# BSPD_v2.net
KiCad netlist of a schematic drawn in Altium Designer
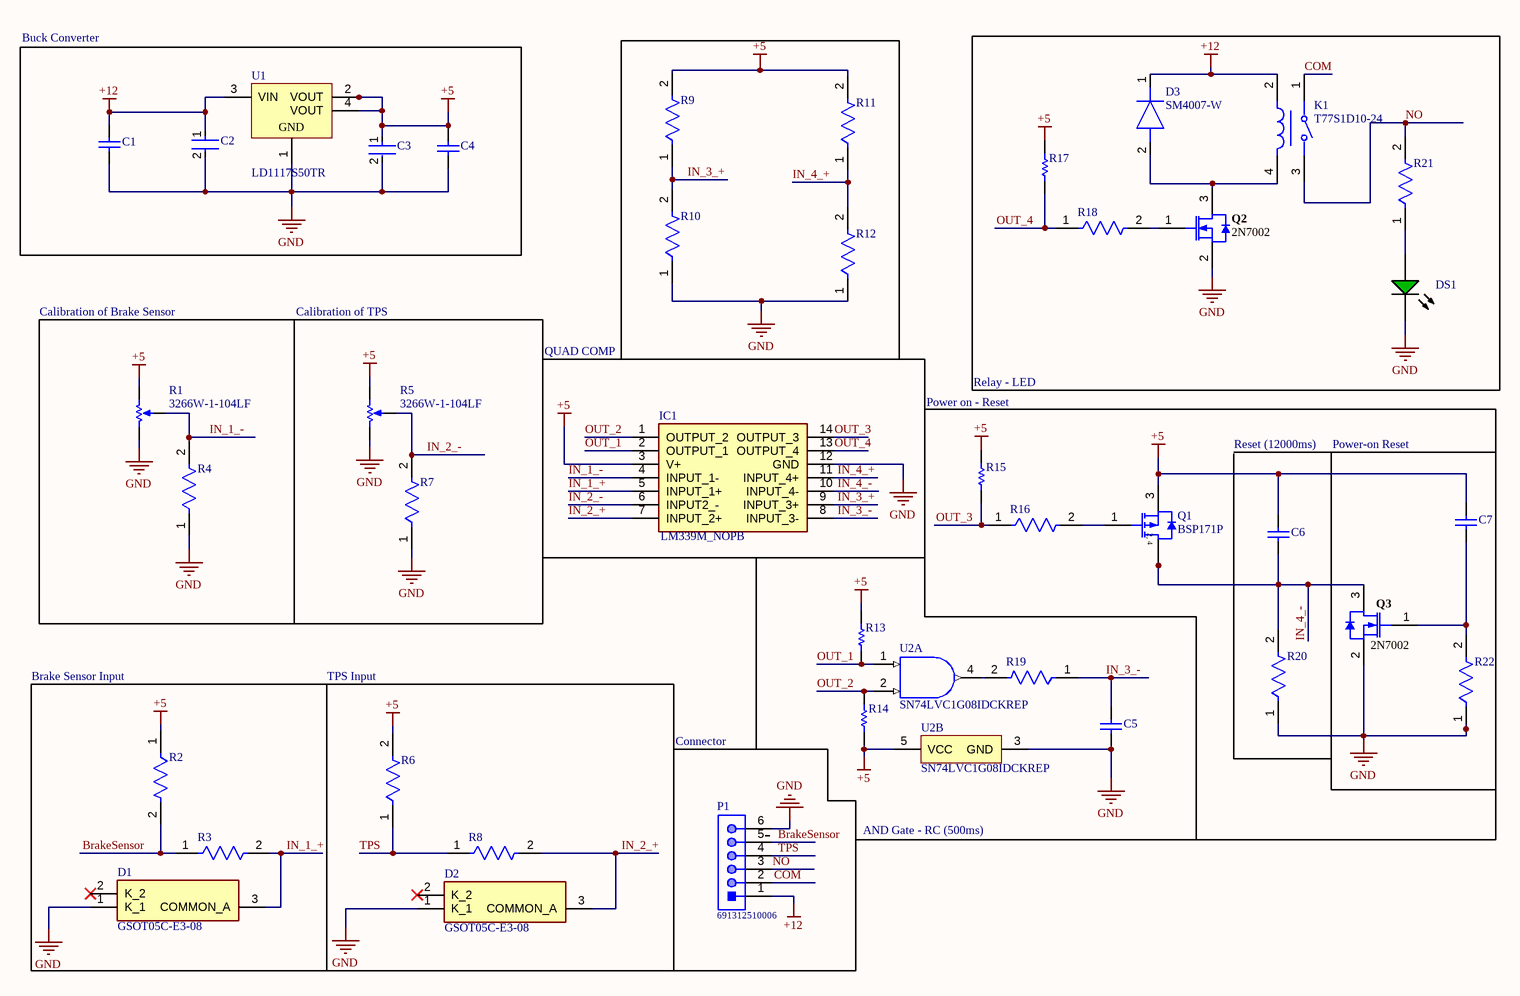
[diagram p0: BSPD v2.SchDoc]

(export (version "E")
  (design (tool "Eeschema 10.0.6"))
  (components
    (comp (ref "C1")
      (value "C1206C106K8RACTU")
      (footprint "CAPC3216X180X50LL20T25")
      (description "Chip Capacitor, 10 uF, +/- 10%, 10 V, -55 to 125 degC, 1206 (3216 Metric), RoHS, Tape and Reel")
      (fields (field (name "TOLERANCE") "10%") (field (name "MANUFACTURER") "Kemet"))
      (libsource (lib "Altium Content Vault") (part "CAP-NP-2"))
    )
    (comp (ref "C2")
      (value "CL21B104KBCNNNC")
      (footprint "FP-CL21-IPC_C")
      (description "CL21 Series 0805 100nF 50V ±10% Tolerance X7R Multilayer Ceramic Chip Capacitor")
      (fields (field (name "TOLERANCE") "10%") (field (name "VOLTAGE") "50V"))
      (libsource (lib "Altium Content Vault") (part "b4654b650e69147ec39a6b967a45e02"))
    )
    (comp (ref "C3")
      (value "CL21B104KBCNNNC")
      (footprint "FP-CL21-IPC_C")
      (description "CL21 Series 0805 100nF 50V ±10% Tolerance X7R Multilayer Ceramic Chip Capacitor")
      (fields (field (name "TOLERANCE") "10%") (field (name "VOLTAGE") "50V"))
      (libsource (lib "Altium Content Vault") (part "b4654b650e69147ec39a6b967a45e02"))
    )
    (comp (ref "C4")
      (value "C1206C106K8RACTU")
      (footprint "CAPC3216X180X50LL20T25")
      (description "Chip Capacitor, 10 uF, +/- 10%, 10 V, -55 to 125 degC, 1206 (3216 Metric), RoHS, Tape and Reel")
      (fields (field (name "TOLERANCE") "10%") (field (name "MANUFACTURER") "Kemet"))
      (libsource (lib "Altium Content Vault") (part "CAP-NP-2"))
    )
    (comp (ref "C5")
      (value "C1206C106K8RACTU")
      (footprint "CAPC3216X180X50LL20T25")
      (description "Chip Capacitor, 10 uF, +/- 10%, 10 V, -55 to 125 degC, 1206 (3216 Metric), RoHS, Tape and Reel")
      (fields (field (name "TOLERANCE") "10%") (field (name "MANUFACTURER") "Kemet"))
      (libsource (lib "Altium Content Vault") (part "CAP-NP-2"))
    )
    (comp (ref "C6")
      (value "C1206C106K8RACTU")
      (footprint "CAPC3216X180X50LL20T25")
      (description "Chip Capacitor, 10 uF, +/- 10%, 10 V, -55 to 125 degC, 1206 (3216 Metric), RoHS, Tape and Reel")
      (fields (field (name "TOLERANCE") "10%") (field (name "MANUFACTURER") "Kemet"))
      (libsource (lib "Altium Content Vault") (part "CAP-NP-2"))
    )
    (comp (ref "C7")
      (value "C1206C106K8RACTU")
      (footprint "CAPC3216X180X50LL20T25")
      (description "Chip Capacitor, 100 nF, +/- 10%, 10 V, -55 to 125 degC, 1206 (3216 Metric), RoHS, Tape and Reel")
      (fields (field (name "TOLERANCE") "10%") (field (name "MANUFACTURER") "Kemet"))
      (libsource (lib "Altium Content Vault") (part "CAP-NP-2"))
    )
    (comp (ref "D1")
      (value "GSOT05C-E3-08")
      (footprint "SamacSys:SOT95P248X115-3N")
      (description "Diode ESD (Uni-directional)")
      (fields (field (name "MOUSER PART NUMBER") "78-GSOT05C-E3-08"))
      (libsource (lib "*") (part "GSOT05C-E3-08"))
    )
    (comp (ref "D2")
      (value "GSOT05C-E3-08")
      (footprint "SamacSys:SOT95P248X115-3N")
      (description "Diode ESD (Uni-directional)")
      (fields (field (name "MOUSER PART NUMBER") "78-GSOT05C-E3-08"))
      (libsource (lib "*") (part "GSOT05C-E3-08"))
    )
    (comp (ref "D3")
      (value "SM4007-W")
      (footprint "SamacSys:SM4007W")
      (description "Diode")
      (fields (field (name "MOUSER PART NUMBER") "583-SM4007"))
      (libsource (lib "*") (part "SM4007-W"))
    )
    (comp (ref "DS1")
      (value "LTST-C170KGKT")
      (footprint "LTST-LTST-C170KGKT-2_V")
      (description "Ultra Bright AlInGaP Chip LED, 75 mW, -55 to 85 degC, 2-Pin SMD (0805), RoHS, Tape and Reel")
      (fields (field (name "MANUFACTURER") "Lite-On"))
      (libsource (lib "Altium Content Vault") (part "LED-GREEN-KA-2"))
    )
    (comp (ref "IC1")
      (value "LM339M_NOPB")
      (footprint "SamacSys:SOIC127P600X175-14N")
      (description "Integrated Circuit")
      (fields
        (field (name "MANUFACTURER_PART_NUMBER") "LM339M/NOPB")
        (field (name "MOUSER PART NUMBER") "926-LM339M/NOPB")
      )
      (libsource (lib "*") (part "LM339M_NOPB"))
    )
    (comp (ref "K1")
      (value "T77S1D10-24")
      (footprint "FP-T77S1D10-24-MFG")
      (description "RELAY GEN PURPOSE SPST 10A 24V")
      (libsource (lib "Altium Content Vault") (part "efdf740da079d6e8343da2175463948"))
    )
    (comp (ref "P1")
      (value "691312510006")
      (footprint "691312510006")
      (description "Serie 312 - 5.08mm Open Horizontal PCB Header WR-TBL, 6 pin")
      (fields (field (name "MANUFACTURER") "Wurth Elektronik") (field (name "PUBLISHER") "WurthElektronik"))
      (libsource (lib "Altium Content Vault") (part "WE-CN-1P-M-R6"))
    )
    (comp (ref "Q1")
      (value "BSP171P")
      (footprint "INF-PG-SOT223_SC-73_N")
      (fields (field (name "MANUFACTURER") "Infineon"))
      (libsource (lib "Altium Content Vault") (part "INF-PEMOS-GDSD-4-A"))
    )
    (comp (ref "Q2")
      (value "2N7002")
      (footprint "INF-PG-SOT23_M")
      (fields (field (name "MANUFACTURER") "Infineon"))
      (libsource (lib "Altium Content Vault") (part "INF-NDMOS-GSD-3"))
    )
    (comp (ref "Q3")
      (value "2N7002")
      (footprint "INF-PG-SOT23_M")
      (fields (field (name "MANUFACTURER") "Infineon"))
      (libsource (lib "Altium Content Vault") (part "INF-NDMOS-GSD-3"))
    )
    (comp (ref "R1")
      (value "3266W-1-104LF")
      (footprint "BOUR-3266W-3_V")
      (description "Square Trimpot Trimming Potentiometer, 100 KOhm, 0.25 W, -55 to 125 degC, 3-Pin THD, RoHS, Tube")
      (fields (field (name "TOLERANCE") "+/-10%") (field (name "MANUFACTURER") "Bourns"))
      (libsource (lib "Altium Content Vault") (part "BOUR-POT-3"))
    )
    (comp (ref "R2")
      (value "CRCW08052K00FKEA")
      (footprint "FP-CRCW0805-e3-IPC_B")
      (description "RES Thick Film, 100kΩ, 1%, 0.125W, 100ppm/°C, 0805")
      (fields (field (name "TOLERANCE") "1%"))
      (libsource (lib "Altium Content Vault") (part "1029c3af85768c4190bb7ad29bc67b5"))
    )
    (comp (ref "R3")
      (value "CRCW08052K00FKEA")
      (footprint "FP-CRCW0805-e3-IPC_B")
      (description "RES Thick Film, 10kΩ, 1%, 0.125W, 100ppm/°C, 0805")
      (fields (field (name "TOLERANCE") "1%"))
      (libsource (lib "Altium Content Vault") (part "1029c3af85768c4190bb7ad29bc67b5"))
    )
    (comp (ref "R4")
      (value "CRCW08052K00FKEA")
      (footprint "FP-CRCW0805-e3-IPC_B")
      (description "RES Thick Film, 10kΩ, 1%, 0.125W, 100ppm/°C, 0805")
      (fields (field (name "TOLERANCE") "1%"))
      (libsource (lib "Altium Content Vault") (part "1029c3af85768c4190bb7ad29bc67b5"))
    )
    (comp (ref "R5")
      (value "3266W-1-104LF")
      (footprint "BOUR-3266W-3_V")
      (description "Square Trimpot Trimming Potentiometer, 100 KOhm, 0.25 W, -55 to 125 degC, 3-Pin THD, RoHS, Tube")
      (fields (field (name "TOLERANCE") "+/-10%") (field (name "MANUFACTURER") "Bourns"))
      (libsource (lib "Altium Content Vault") (part "BOUR-POT-3"))
    )
    (comp (ref "R6")
      (value "CRCW08052K00FKEA")
      (footprint "FP-CRCW0805-e3-IPC_B")
      (description "RES Thick Film, 100kΩ, 1%, 0.125W, 100ppm/°C, 0805")
      (fields (field (name "TOLERANCE") "1%"))
      (libsource (lib "Altium Content Vault") (part "1029c3af85768c4190bb7ad29bc67b5"))
    )
    (comp (ref "R7")
      (value "CRCW08052K00FKEA")
      (footprint "FP-CRCW0805-e3-IPC_B")
      (description "RES Thick Film, 10kΩ, 1%, 0.125W, 100ppm/°C, 0805")
      (fields (field (name "TOLERANCE") "1%"))
      (libsource (lib "Altium Content Vault") (part "1029c3af85768c4190bb7ad29bc67b5"))
    )
    (comp (ref "R8")
      (value "CRCW08052K00FKEA")
      (footprint "FP-CRCW0805-e3-IPC_B")
      (description "RES Thick Film, 10kΩ, 1%, 0.125W, 100ppm/°C, 0805")
      (fields (field (name "TOLERANCE") "1%"))
      (libsource (lib "Altium Content Vault") (part "1029c3af85768c4190bb7ad29bc67b5"))
    )
    (comp (ref "R9")
      (value "CRCW08052K00FKEA")
      (footprint "FP-CRCW0805-e3-IPC_B")
      (description "RES Thick Film, 39kΩ, 1%, 0.125W, 100ppm/°C, 0805")
      (fields (field (name "TOLERANCE") "1%"))
      (libsource (lib "Altium Content Vault") (part "1029c3af85768c4190bb7ad29bc67b5"))
    )
    (comp (ref "R10")
      (value "CRCW08052K00FKEA")
      (footprint "FP-CRCW0805-e3-IPC_B")
      (description "RES Thick Film, 100kΩ, 1%, 0.125W, 100ppm/°C, 0805")
      (fields (field (name "TOLERANCE") "1%"))
      (libsource (lib "Altium Content Vault") (part "1029c3af85768c4190bb7ad29bc67b5"))
    )
    (comp (ref "R11")
      (value "CRCW08052K00FKEA")
      (footprint "FP-CRCW0805-e3-IPC_B")
      (description "RES Thick Film, 39kΩ, 1%, 0.125W, 100ppm/°C, 0805")
      (fields (field (name "TOLERANCE") "1%"))
      (libsource (lib "Altium Content Vault") (part "1029c3af85768c4190bb7ad29bc67b5"))
    )
    (comp (ref "R12")
      (value "CRCW08052K00FKEA")
      (footprint "FP-CRCW0805-e3-IPC_B")
      (description "RES Thick Film, 10kΩ, 1%, 0.125W, 100ppm/°C, 0805")
      (fields (field (name "TOLERANCE") "1%"))
      (libsource (lib "Altium Content Vault") (part "1029c3af85768c4190bb7ad29bc67b5"))
    )
    (comp (ref "R13")
      (value "TNPW08053K00BEEA")
      (footprint "RESC2013X55X40NL15T20")
      (fields (field (name "MANUFACTURER") "Vishay Dale"))
      (libsource (lib "Altium Content Vault") (part "RES"))
    )
    (comp (ref "R14")
      (value "TNPW08053K00BEEA")
      (footprint "RESC2013X55X40NL15T20")
      (fields (field (name "MANUFACTURER") "Vishay Dale"))
      (libsource (lib "Altium Content Vault") (part "RES"))
    )
    (comp (ref "R15")
      (value "TNPW08053K00BEEA")
      (footprint "RESC2013X55X40NL15T20")
      (fields (field (name "MANUFACTURER") "Vishay Dale"))
      (libsource (lib "Altium Content Vault") (part "RES"))
    )
    (comp (ref "R16")
      (value "CRCW08052K00FKEA")
      (footprint "FP-CRCW0805-e3-IPC_B")
      (description "RES Thick Film, 100Ω, 1%, 0.125W, 100ppm/°C, 0805")
      (fields (field (name "TOLERANCE") "1%"))
      (libsource (lib "Altium Content Vault") (part "1029c3af85768c4190bb7ad29bc67b5"))
    )
    (comp (ref "R17")
      (value "TNPW08053K00BEEA")
      (footprint "RESC2013X55X40NL15T20")
      (fields (field (name "MANUFACTURER") "Vishay Dale"))
      (libsource (lib "Altium Content Vault") (part "RES"))
    )
    (comp (ref "R18")
      (value "CRCW08052K00FKEA")
      (footprint "FP-CRCW0805-e3-IPC_B")
      (description "RES Thick Film, 100Ω, 1%, 0.125W, 100ppm/°C, 0805")
      (fields (field (name "TOLERANCE") "1%"))
      (libsource (lib "Altium Content Vault") (part "1029c3af85768c4190bb7ad29bc67b5"))
    )
    (comp (ref "R19")
      (value "CRCW08052K00FKEA")
      (footprint "FP-CRCW0805-e3-IPC_B")
      (description "RES Thick Film, 39kΩ, 1%, 0.125W, 100ppm/°C, 0805")
      (fields (field (name "TOLERANCE") "1%"))
      (libsource (lib "Altium Content Vault") (part "1029c3af85768c4190bb7ad29bc67b5"))
    )
    (comp (ref "R20")
      (value "CR0805-JW-125ELF")
      (footprint "FP-CR0805-IPC_A")
      (description "Thick Film Chip Resistors 0805 1.2MΩ 0.125W 5% 200ppm/°C")
      (fields (field (name "TOLERANCE") "5%"))
      (libsource (lib "Altium Content Vault") (part "1029c3af85768c4190bb7ad29bc67b5"))
    )
    (comp (ref "R21")
      (value "CRCW08052K00FKEA")
      (footprint "FP-CRCW0805-e3-IPC_B")
      (description "RES Thick Film, 360Ω, 1%, 0.125W, 100ppm/°C, 0805")
      (fields (field (name "TOLERANCE") "1%"))
      (libsource (lib "Altium Content Vault") (part "1029c3af85768c4190bb7ad29bc67b5"))
    )
    (comp (ref "R22")
      (value "CRCW08052K00FKEA")
      (footprint "FP-CRCW0805-e3-IPC_B")
      (description "RES Thick Film, 560kΩ, 1%, 0.125W, 100ppm/°C, 0805")
      (fields (field (name "TOLERANCE") "1%"))
      (libsource (lib "Altium Content Vault") (part "1029c3af85768c4190bb7ad29bc67b5"))
    )
    (comp (ref "U1")
      (value "LD1117S50TR")
      (footprint "SOT-223_L")
      (description "Fixed Low Drop Positive Voltage Regulator, 5V, 4-Pin SOT-223, Tape and Reel")
      (libsource (lib "Altium Content Vault") (part "PM-REG-LD1117-SOT4"))
    )
    (comp (ref "U2")
      (value "SN74LVC1G08IDCKREP")
      (footprint "DCK0005A_L")
      (description "Enhanced Product Single 2-Input Positive-And Gate, DCK0005A, LARGE T&R")
      (fields
        (field (name "GENERIC PART NUMBER") "SN74LVC1G08-EP")
        (field (name "MANUFACTURER") "Texas Instruments")
      )
      (libsource (lib "Altium Content Vault") (part "TI-SN74XXX1X08-5"))
    )
  )
  (nets
    (net (code "1") (name "+5") (class "Default")
      (node (ref "C3") (pin "1") (pinfunction "1_1") (pintype "passive"))
      (node (ref "C4") (pin "2") (pinfunction "2_2") (pintype "passive"))
      (node (ref "C6") (pin "2") (pinfunction "2_2") (pintype "passive"))
      (node (ref "C7") (pin "2") (pinfunction "2_2") (pintype "passive"))
      (node (ref "IC1") (pin "3") (pinfunction "V+_3") (pintype "passive"))
      (node (ref "Q1") (pin "3") (pinfunction "SOURCE_3") (pintype "passive"))
      (node (ref "R1") (pin "1") (pinfunction "CCW_1") (pintype "passive"))
      (node (ref "R11") (pin "2") (pinfunction "2_2") (pintype "passive"))
      (node (ref "R13") (pin "2") (pinfunction "2_2") (pintype "passive"))
      (node (ref "R14") (pin "2") (pinfunction "2_2") (pintype "passive"))
      (node (ref "R15") (pin "2") (pinfunction "2_2") (pintype "passive"))
      (node (ref "R17") (pin "2") (pinfunction "2_2") (pintype "passive"))
      (node (ref "R2") (pin "1") (pinfunction "1_1") (pintype "passive"))
      (node (ref "R5") (pin "1") (pinfunction "CCW_1") (pintype "passive"))
      (node (ref "R6") (pin "2") (pinfunction "2_2") (pintype "passive"))
      (node (ref "R9") (pin "2") (pinfunction "2_2") (pintype "passive"))
      (node (ref "U1") (pin "2") (pinfunction "VOUT_2") (pintype "power_in"))
      (node (ref "U1") (pin "4") (pinfunction "VOUT_4") (pintype "power_in"))
      (node (ref "U2") (pin "5") (pinfunction "VCC_5") (pintype "power_in"))
    )
    (net (code "2") (name "+12") (class "Default")
      (node (ref "C1") (pin "2") (pinfunction "2_2") (pintype "passive"))
      (node (ref "C2") (pin "1") (pinfunction "1_1") (pintype "passive"))
      (node (ref "D3") (pin "1") (pinfunction "K_1") (pintype "passive"))
      (node (ref "K1") (pin "2") (pinfunction "2_2") (pintype "passive"))
      (node (ref "P1") (pin "1") (pinfunction "1_1") (pintype "passive"))
      (node (ref "U1") (pin "3") (pinfunction "VIN_3") (pintype "power_in"))
    )
    (net (code "3") (name "/BrakeSensor") (class "Default")
      (node (ref "P1") (pin "5") (pinfunction "5_5") (pintype "passive"))
      (node (ref "R2") (pin "2") (pinfunction "2_2") (pintype "passive"))
      (node (ref "R3") (pin "1") (pinfunction "1_1") (pintype "passive"))
    )
    (net (code "4") (name "/COM") (class "Default")
      (node (ref "K1") (pin "1") (pinfunction "1_1") (pintype "passive"))
      (node (ref "P1") (pin "2") (pinfunction "2_2") (pintype "passive"))
    )
    (net (code "5") (name "/IN_1_+") (class "Default")
      (node (ref "D1") (pin "3") (pinfunction "COMMON_A_3") (pintype "passive"))
      (node (ref "IC1") (pin "5") (pinfunction "INPUT_1+_5") (pintype "passive"))
      (node (ref "R3") (pin "2") (pinfunction "2_2") (pintype "passive"))
    )
    (net (code "6") (name "/IN_1_-") (class "Default")
      (node (ref "IC1") (pin "4") (pinfunction "INPUT_1-_4") (pintype "passive"))
      (node (ref "R1") (pin "2") (pinfunction "WIPER_2") (pintype "passive"))
      (node (ref "R4") (pin "2") (pinfunction "2_2") (pintype "passive"))
    )
    (net (code "7") (name "/IN_2_+") (class "Default")
      (node (ref "D2") (pin "3") (pinfunction "COMMON_A_3") (pintype "passive"))
      (node (ref "IC1") (pin "7") (pinfunction "INPUT_2+_7") (pintype "passive"))
      (node (ref "R8") (pin "2") (pinfunction "2_2") (pintype "passive"))
    )
    (net (code "8") (name "/IN_2_-") (class "Default")
      (node (ref "IC1") (pin "6") (pinfunction "INPUT2_-_6") (pintype "passive"))
      (node (ref "R5") (pin "2") (pinfunction "WIPER_2") (pintype "passive"))
      (node (ref "R7") (pin "2") (pinfunction "2_2") (pintype "passive"))
    )
    (net (code "9") (name "/IN_3_+") (class "Default")
      (node (ref "IC1") (pin "9") (pinfunction "INPUT_3+_9") (pintype "passive"))
      (node (ref "R10") (pin "2") (pinfunction "2_2") (pintype "passive"))
      (node (ref "R9") (pin "1") (pinfunction "1_1") (pintype "passive"))
    )
    (net (code "10") (name "/IN_3_-") (class "Default")
      (node (ref "C5") (pin "2") (pinfunction "2_2") (pintype "passive"))
      (node (ref "IC1") (pin "8") (pinfunction "INPUT_3-_8") (pintype "passive"))
      (node (ref "R19") (pin "1") (pinfunction "1_1") (pintype "passive"))
    )
    (net (code "11") (name "/IN_4_+") (class "Default")
      (node (ref "IC1") (pin "11") (pinfunction "INPUT_4+_11") (pintype "passive"))
      (node (ref "R11") (pin "1") (pinfunction "1_1") (pintype "passive"))
      (node (ref "R12") (pin "2") (pinfunction "2_2") (pintype "passive"))
    )
    (net (code "12") (name "/IN_4_-") (class "Default")
      (node (ref "C6") (pin "1") (pinfunction "1_1") (pintype "passive"))
      (node (ref "IC1") (pin "10") (pinfunction "INPUT_4-_10") (pintype "passive"))
      (node (ref "Q1") (pin "2") (pinfunction "DRAIN_2") (pintype "passive"))
      (node (ref "Q1") (pin "4") (pinfunction "DRAIN_4") (pintype "passive"))
      (node (ref "Q3") (pin "3") (pinfunction "DRAIN_3") (pintype "passive"))
      (node (ref "R20") (pin "2") (pinfunction "2_2") (pintype "passive"))
    )
    (net (code "13") (name "/NO") (class "Default")
      (node (ref "K1") (pin "3") (pinfunction "3_3") (pintype "passive"))
      (node (ref "P1") (pin "3") (pinfunction "3_3") (pintype "passive"))
      (node (ref "R21") (pin "2") (pinfunction "2_2") (pintype "passive"))
    )
    (net (code "14") (name "/OUT_1") (class "Default")
      (node (ref "IC1") (pin "2") (pinfunction "OUTPUT_1_2") (pintype "passive"))
      (node (ref "R13") (pin "1") (pinfunction "1_1") (pintype "passive"))
      (node (ref "U2") (pin "1") (pinfunction "A_1") (pintype "input"))
    )
    (net (code "15") (name "/OUT_2") (class "Default")
      (node (ref "IC1") (pin "1") (pinfunction "OUTPUT_2_1") (pintype "passive"))
      (node (ref "R14") (pin "1") (pinfunction "1_1") (pintype "passive"))
      (node (ref "U2") (pin "2") (pinfunction "B_2") (pintype "input"))
    )
    (net (code "16") (name "/OUT_3") (class "Default")
      (node (ref "IC1") (pin "14") (pinfunction "OUTPUT_3_14") (pintype "passive"))
      (node (ref "R15") (pin "1") (pinfunction "1_1") (pintype "passive"))
      (node (ref "R16") (pin "1") (pinfunction "1_1") (pintype "passive"))
    )
    (net (code "17") (name "/OUT_4") (class "Default")
      (node (ref "IC1") (pin "13") (pinfunction "OUTPUT_4_13") (pintype "passive"))
      (node (ref "R17") (pin "1") (pinfunction "1_1") (pintype "passive"))
      (node (ref "R18") (pin "1") (pinfunction "1_1") (pintype "passive"))
    )
    (net (code "18") (name "/TPS") (class "Default")
      (node (ref "P1") (pin "4") (pinfunction "4_4") (pintype "passive"))
      (node (ref "R6") (pin "1") (pinfunction "1_1") (pintype "passive"))
      (node (ref "R8") (pin "1") (pinfunction "1_1") (pintype "passive"))
    )
    (net (code "19") (name "GND") (class "Default")
      (node (ref "C1") (pin "1") (pinfunction "1_1") (pintype "passive"))
      (node (ref "C2") (pin "2") (pinfunction "2_2") (pintype "passive"))
      (node (ref "C3") (pin "2") (pinfunction "2_2") (pintype "passive"))
      (node (ref "C4") (pin "1") (pinfunction "1_1") (pintype "passive"))
      (node (ref "C5") (pin "1") (pinfunction "1_1") (pintype "passive"))
      (node (ref "D1") (pin "1") (pinfunction "K_1_1") (pintype "passive"))
      (node (ref "D2") (pin "1") (pinfunction "K_1_1") (pintype "passive"))
      (node (ref "DS1") (pin "1") (pinfunction "K_1") (pintype "passive"))
      (node (ref "IC1") (pin "12") (pinfunction "GND_12") (pintype "passive"))
      (node (ref "P1") (pin "6") (pinfunction "6_6") (pintype "passive"))
      (node (ref "Q2") (pin "2") (pinfunction "SOURCE_2") (pintype "passive"))
      (node (ref "Q3") (pin "2") (pinfunction "SOURCE_2") (pintype "passive"))
      (node (ref "R1") (pin "3") (pinfunction "CW_3") (pintype "passive"))
      (node (ref "R10") (pin "1") (pinfunction "1_1") (pintype "passive"))
      (node (ref "R12") (pin "1") (pinfunction "1_1") (pintype "passive"))
      (node (ref "R20") (pin "1") (pinfunction "1_1") (pintype "passive"))
      (node (ref "R22") (pin "1") (pinfunction "1_1") (pintype "passive"))
      (node (ref "R4") (pin "1") (pinfunction "1_1") (pintype "passive"))
      (node (ref "R5") (pin "3") (pinfunction "CW_3") (pintype "passive"))
      (node (ref "R7") (pin "1") (pinfunction "1_1") (pintype "passive"))
      (node (ref "U1") (pin "1") (pinfunction "GND_1") (pintype "power_in"))
      (node (ref "U2") (pin "3") (pinfunction "GND_3") (pintype "power_in"))
    )
    (net (code "20") (name "Net-(D3-A)") (class "Default")
      (node (ref "D3") (pin "2") (pinfunction "A_2") (pintype "passive"))
      (node (ref "K1") (pin "4") (pinfunction "4_4") (pintype "passive"))
      (node (ref "Q2") (pin "3") (pinfunction "DRAIN_3") (pintype "passive"))
    )
    (net (code "21") (name "Net-(DS1-A)") (class "Default")
      (node (ref "DS1") (pin "2") (pinfunction "A_2") (pintype "passive"))
      (node (ref "R21") (pin "1") (pinfunction "1_1") (pintype "passive"))
    )
    (net (code "22") (name "Net-(Q1-GATE)") (class "Default")
      (node (ref "Q1") (pin "1") (pinfunction "GATE_1") (pintype "passive"))
      (node (ref "R16") (pin "2") (pinfunction "2_2") (pintype "passive"))
    )
    (net (code "23") (name "Net-(Q2-GATE)") (class "Default")
      (node (ref "Q2") (pin "1") (pinfunction "GATE_1") (pintype "passive"))
      (node (ref "R18") (pin "2") (pinfunction "2_2") (pintype "passive"))
    )
    (net (code "24") (name "Net-(Q3-GATE)") (class "Default")
      (node (ref "C7") (pin "1") (pinfunction "1_1") (pintype "passive"))
      (node (ref "Q3") (pin "1") (pinfunction "GATE_1") (pintype "passive"))
      (node (ref "R22") (pin "2") (pinfunction "2_2") (pintype "passive"))
    )
    (net (code "25") (name "Net-(U2A-Y)") (class "Default")
      (node (ref "R19") (pin "2") (pinfunction "2_2") (pintype "passive"))
      (node (ref "U2") (pin "4") (pinfunction "Y_4") (pintype "output"))
    )
    (net (code "26") (name "unconnected-(D1-K_2-Pad2)") (class "Default")
      (node (ref "D1") (pin "2") (pinfunction "K_2_2") (pintype "passive+no_connect"))
    )
    (net (code "27") (name "unconnected-(D2-K_2-Pad2)") (class "Default")
      (node (ref "D2") (pin "2") (pinfunction "K_2_2") (pintype "passive+no_connect"))
    )
  )
)
